# Sheet3_MCU.net
KiCad netlist of a schematic drawn in Altium Designer
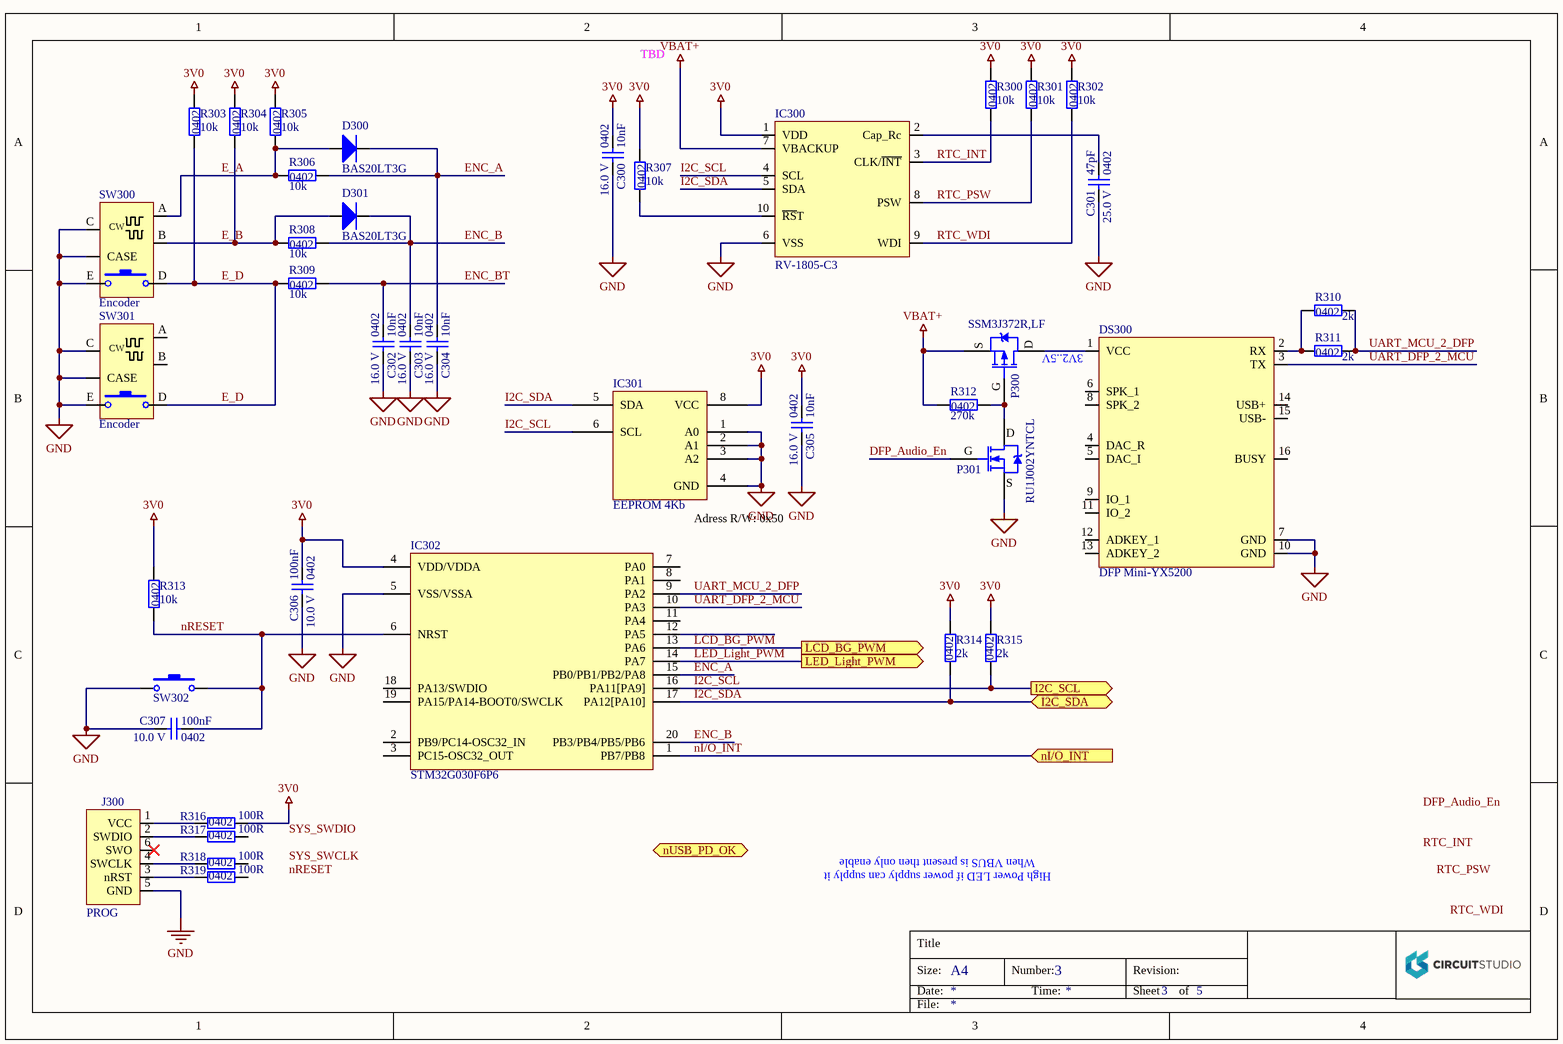
[diagram p0: Sheet3_MCU.SchDoc]

(export (version "E")
  (design (tool "Eeschema 10.0.6"))
  (components
    (comp (ref "C300")
      (value "C 10nF 0402 16V")
      (footprint "0402")
      (description "CAP CER 10000PF 16V Y5V 0402")
      (fields
        (field (name "MANUFACTURER") "Samsung Electro-Mechanics")
        (field (name "MANUFACTURER PART NUMBER") "CL05F103ZO5NNNC")
        (field (name "CAPACITANCE") "10nF")
        (field (name "VOLTAGE") "16.0 V")
      )
      (libsource (lib "CS_Part_Library") (part "CAP_10nF_16V_0402"))
    )
    (comp (ref "C301")
      (value "C 47pF 0402 25V")
      (footprint "0402")
      (description "CAP CER 47PF 25V C0G/NP0 0402")
      (fields
        (field (name "MANUFACTURER") "KEMET")
        (field (name "MANUFACTURER PART NUMBER") "C0402C470J3GAC7867")
        (field (name "CAPACITANCE") "47pF")
        (field (name "VOLTAGE") "25.0 V")
      )
      (libsource (lib "CS_Part_Library") (part "CAP_47pF_25V_0402"))
    )
    (comp (ref "C302")
      (value "C 10nF 0402 16V")
      (footprint "0402")
      (description "CAP CER 10000PF 16V Y5V 0402")
      (fields
        (field (name "MANUFACTURER") "Samsung Electro-Mechanics")
        (field (name "MANUFACTURER PART NUMBER") "CL05F103ZO5NNNC")
        (field (name "CAPACITANCE") "10nF")
        (field (name "VOLTAGE") "16.0 V")
      )
      (libsource (lib "CS_Part_Library") (part "CAP_10nF_16V_0402"))
    )
    (comp (ref "C303")
      (value "C 10nF 0402 16V")
      (footprint "0402")
      (description "CAP CER 10000PF 16V Y5V 0402")
      (fields
        (field (name "MANUFACTURER") "Samsung Electro-Mechanics")
        (field (name "MANUFACTURER PART NUMBER") "CL05F103ZO5NNNC")
        (field (name "CAPACITANCE") "10nF")
        (field (name "VOLTAGE") "16.0 V")
      )
      (libsource (lib "CS_Part_Library") (part "CAP_10nF_16V_0402"))
    )
    (comp (ref "C304")
      (value "C 10nF 0402 16V")
      (footprint "0402")
      (description "CAP CER 10000PF 16V Y5V 0402")
      (fields
        (field (name "MANUFACTURER") "Samsung Electro-Mechanics")
        (field (name "MANUFACTURER PART NUMBER") "CL05F103ZO5NNNC")
        (field (name "CAPACITANCE") "10nF")
        (field (name "VOLTAGE") "16.0 V")
      )
      (libsource (lib "CS_Part_Library") (part "CAP_10nF_16V_0402"))
    )
    (comp (ref "C305")
      (value "C 10nF 0402 16V")
      (footprint "0402")
      (description "CAP CER 10000PF 16V Y5V 0402")
      (fields
        (field (name "MANUFACTURER") "Samsung Electro-Mechanics")
        (field (name "MANUFACTURER PART NUMBER") "CL05F103ZO5NNNC")
        (field (name "CAPACITANCE") "10nF")
        (field (name "VOLTAGE") "16.0 V")
      )
      (libsource (lib "CS_Part_Library") (part "CAP_10nF_16V_0402"))
    )
    (comp (ref "C306")
      (value "C 100nF 0402 10V")
      (footprint "0402")
      (description "CAP CER 0.1UF 10V X5R 0402")
      (fields
        (field (name "MANUFACTURER") "Samsung Electro-Mechanics")
        (field (name "MANUFACTURER PART NUMBER") "CL05A104MP5NNNC")
        (field (name "CAPACITANCE") "100nF")
        (field (name "VOLTAGE") "10.0 V")
      )
      (libsource (lib "CS_Part_Library") (part "CAP_100nF_10V_0402"))
    )
    (comp (ref "C307")
      (value "C 100nF 0402 10V")
      (footprint "0402")
      (description "CAP CER 0.1UF 10V X5R 0402")
      (fields
        (field (name "MANUFACTURER") "Samsung Electro-Mechanics")
        (field (name "MANUFACTURER PART NUMBER") "CL05A104MP5NNNC")
        (field (name "CAPACITANCE") "100nF")
        (field (name "VOLTAGE") "10.0 V")
      )
      (libsource (lib "CS_Part_Library") (part "CAP_100nF_10V_0402"))
    )
    (comp (ref "D300")
      (value "BAS20LT3G")
      (footprint "SOT-23-3")
      (description "DIODE GP 200V 200MA SOT23-3")
      (fields (field (name "MANUFACTURER") "onsemi") (field (name "MANUFACTURER PART NUMBER") "BAS20LT3G"))
      (libsource (lib "Symbols") (part "D_LL_200V_200mA"))
    )
    (comp (ref "D301")
      (value "BAS20LT3G")
      (footprint "SOT-23-3")
      (description "DIODE GP 200V 200MA SOT23-3")
      (fields (field (name "MANUFACTURER") "onsemi") (field (name "MANUFACTURER PART NUMBER") "BAS20LT3G"))
      (libsource (lib "Symbols") (part "D_LL_200V_200mA"))
    )
    (comp (ref "DS300")
      (value "DFP Mini-YX5200")
      (footprint "DFP_Player_Mini")
      (description "Mini-YX5200 Audio MP3 Modul")
      (fields (field (name "MANUFACTURER") "DFRobot") (field (name "MANUFACTURER PART NUMBER") "DFR0299"))
      (libsource (lib "CS_Part_Library") (part "DFP_Player_mini"))
    )
    (comp (ref "IC300")
      (value "RV-1805-C3")
      (footprint "SON-6")
      (description "IC RTC CLK/CALENDAR I2C 10SON")
      (fields
        (field (name "MANUFACTURER") "Micro Crystal AG")
        (field (name "MANUFACTURER PART NUMBER") "RV-1805-C3-32.768KHZ-2PPM-TA-QA")
      )
      (libsource (lib "CS_Part_Library") (part "IC_RTC_1805-C3"))
    )
    (comp (ref "IC301")
      (value "EEPROM 4Kb")
      (footprint "TSSOP-8_4.4mm")
      (description "IC EEPROM 4KBIT I2C 1MHZ 8TSSOP")
      (fields
        (field (name "MANUFACTURER") "Microchip Technology")
        (field (name "MANUFACTURER PART NUMBER") "AT34C04-X5M-T")
      )
      (libsource (lib "CS_Part_Library") (part "IC_EEPROM_4Kb"))
    )
    (comp (ref "IC302")
      (value "STM32G030F6P6")
      (footprint "TSSOP-20")
      (description "IC MCU 32BIT 32KB FLASH 20TSSOP")
      (fields (field (name "MANUFACTURER") "STMicroelectronics"))
      (libsource (lib "CS_Part_Library") (part "IC_MCU_STM32G030F6P6"))
    )
    (comp (ref "J300")
      (value "PROG")
      (footprint "J_TC2030-IDC-FP")
      (description "SWD Programmer")
      (fields (field (name "MANUFACTURER") "Tag_connect") (field (name "MANUFACTURER PART NUMBER") "TC2030"))
      (libsource (lib "CS_Part_Library") (part "J_TC2030-IDC-FP"))
    )
    (comp (ref "P300")
      (value "P PMOS 30V 6A")
      (footprint "SOT-23-3-F")
      (description "MOSFET P-CH 30V 6A SOT23F")
      (fields
        (field (name "MANUFACTURER") "Toshiba Semiconductor and Storage")
        (field (name "MANUFACTURER PART NUMBER") "SSM3J372R,LF")
      )
      (libsource (lib "CS_Part_Library") (part "P_PCH_30V_1W"))
    )
    (comp (ref "P301")
      (value "P_NCH_50V_150mW")
      (footprint "UMT3F")
      (description "MOSFET N-CH 50V 200MA UMT3F")
      (fields
        (field (name "MANUFACTURER") "Rohm Semiconductor")
        (field (name "MANUFACTURER PART NUMBER") "RU1J002YNTCL")
      )
      (libsource (lib "CS_Part_Library") (part "P_NCH_50V_150mW"))
    )
    (comp (ref "R300")
      (value "R 10k 0402")
      (footprint "0402")
      (description "RES 10K OHM 1% 1/16W 0402")
      (fields
        (field (name "MANUFACTURER") "YAGEO")
        (field (name "MANUFACTURER PART NUMBER") "RC0402FR-0710KL")
        (field (name "RESISTANCE") "10k")
      )
      (libsource (lib "") (part "R_10k_0402_1"))
    )
    (comp (ref "R301")
      (value "R 10k 0402")
      (footprint "0402")
      (description "RES 10K OHM 1% 1/16W 0402")
      (fields
        (field (name "MANUFACTURER") "YAGEO")
        (field (name "MANUFACTURER PART NUMBER") "RC0402FR-0710KL")
        (field (name "RESISTANCE") "10k")
      )
      (libsource (lib "") (part "R_10k_0402_1"))
    )
    (comp (ref "R302")
      (value "R 10k 0402")
      (footprint "0402")
      (description "RES 10K OHM 1% 1/16W 0402")
      (fields
        (field (name "MANUFACTURER") "YAGEO")
        (field (name "MANUFACTURER PART NUMBER") "RC0402FR-0710KL")
        (field (name "RESISTANCE") "10k")
      )
      (libsource (lib "") (part "R_10k_0402_1"))
    )
    (comp (ref "R303")
      (value "R 10k 0402")
      (footprint "0402")
      (description "RES 10K OHM 1% 1/16W 0402")
      (fields
        (field (name "MANUFACTURER") "YAGEO")
        (field (name "MANUFACTURER PART NUMBER") "RC0402FR-0710KL")
        (field (name "RESISTANCE") "10k")
      )
      (libsource (lib "") (part "R_10k_0402_1"))
    )
    (comp (ref "R304")
      (value "R 10k 0402")
      (footprint "0402")
      (description "RES 10K OHM 1% 1/16W 0402")
      (fields
        (field (name "MANUFACTURER") "YAGEO")
        (field (name "MANUFACTURER PART NUMBER") "RC0402FR-0710KL")
        (field (name "RESISTANCE") "10k")
      )
      (libsource (lib "") (part "R_10k_0402_1"))
    )
    (comp (ref "R305")
      (value "R 10k 0402")
      (footprint "0402")
      (description "RES 10K OHM 1% 1/16W 0402")
      (fields
        (field (name "MANUFACTURER") "YAGEO")
        (field (name "MANUFACTURER PART NUMBER") "RC0402FR-0710KL")
        (field (name "RESISTANCE") "10k")
      )
      (libsource (lib "") (part "R_10k_0402_1"))
    )
    (comp (ref "R306")
      (value "R 10k 0402")
      (footprint "0402")
      (description "RES 10K OHM 1% 1/16W 0402")
      (fields
        (field (name "MANUFACTURER") "YAGEO")
        (field (name "MANUFACTURER PART NUMBER") "RC0402FR-0710KL")
        (field (name "RESISTANCE") "10k")
      )
      (libsource (lib "CS_Part_Library") (part "R_10k_0402"))
    )
    (comp (ref "R307")
      (value "R 10k 0402")
      (footprint "0402")
      (description "RES 10K OHM 1% 1/16W 0402")
      (fields
        (field (name "MANUFACTURER") "YAGEO")
        (field (name "MANUFACTURER PART NUMBER") "RC0402FR-0710KL")
        (field (name "RESISTANCE") "10k")
      )
      (libsource (lib "") (part "R_10k_0402_1"))
    )
    (comp (ref "R308")
      (value "R 10k 0402")
      (footprint "0402")
      (description "RES 10K OHM 1% 1/16W 0402")
      (fields
        (field (name "MANUFACTURER") "YAGEO")
        (field (name "MANUFACTURER PART NUMBER") "RC0402FR-0710KL")
        (field (name "RESISTANCE") "10k")
      )
      (libsource (lib "CS_Part_Library") (part "R_10k_0402"))
    )
    (comp (ref "R309")
      (value "R 10k 0402")
      (footprint "0402")
      (description "RES 10K OHM 1% 1/16W 0402")
      (fields
        (field (name "MANUFACTURER") "YAGEO")
        (field (name "MANUFACTURER PART NUMBER") "RC0402FR-0710KL")
        (field (name "RESISTANCE") "10k")
      )
      (libsource (lib "CS_Part_Library") (part "R_10k_0402"))
    )
    (comp (ref "R310")
      (value "R 2k 0402")
      (footprint "0402")
      (description "RES 2K OHM 1% 1/16W 0402")
      (fields
        (field (name "MANUFACTURER") "Stackpole Electronics Inc")
        (field (name "MANUFACTURER PART NUMBER") "RMCF0402FT2K00")
        (field (name "RESISTANCE") "2k")
      )
      (libsource (lib "") (part "R_2k_0402_1"))
    )
    (comp (ref "R311")
      (value "R 2k 0402")
      (footprint "0402")
      (description "RES 2K OHM 1% 1/16W 0402")
      (fields
        (field (name "MANUFACTURER") "Stackpole Electronics Inc")
        (field (name "MANUFACTURER PART NUMBER") "RMCF0402FT2K00")
        (field (name "RESISTANCE") "2k")
      )
      (libsource (lib "") (part "R_2k_0402_1"))
    )
    (comp (ref "R312")
      (value "R 270k 0402")
      (footprint "0402")
      (description "RES 270K OHM 1% 1/16W 0402")
      (fields
        (field (name "MANUFACTURER") "YAGEO")
        (field (name "MANUFACTURER PART NUMBER") "RC0402FR-07270KL")
        (field (name "RESISTANCE") "270k")
      )
      (libsource (lib "CS_Part_Library") (part "R_270k_0402"))
    )
    (comp (ref "R313")
      (value "R 10k 0402")
      (footprint "0402")
      (description "RES 10K OHM 1% 1/16W 0402")
      (fields
        (field (name "MANUFACTURER") "YAGEO")
        (field (name "MANUFACTURER PART NUMBER") "RC0402FR-0710KL")
        (field (name "RESISTANCE") "10k")
      )
      (libsource (lib "") (part "R_10k_0402_1"))
    )
    (comp (ref "R314")
      (value "R 2k 0402")
      (footprint "0402")
      (description "RES 2K OHM 1% 1/16W 0402")
      (fields
        (field (name "MANUFACTURER") "Stackpole Electronics Inc")
        (field (name "MANUFACTURER PART NUMBER") "RMCF0402FT2K00")
        (field (name "RESISTANCE") "2k")
      )
      (libsource (lib "CS_Part_Library") (part "R_2k_0402"))
    )
    (comp (ref "R315")
      (value "R 2k 0402")
      (footprint "0402")
      (description "RES 2K OHM 1% 1/16W 0402")
      (fields
        (field (name "MANUFACTURER") "Stackpole Electronics Inc")
        (field (name "MANUFACTURER PART NUMBER") "RMCF0402FT2K00")
        (field (name "RESISTANCE") "2k")
      )
      (libsource (lib "CS_Part_Library") (part "R_2k_0402"))
    )
    (comp (ref "R316")
      (value "R 100R 0402")
      (footprint "0402")
      (description "RES 100 OHM 1% 1/16W 0402")
      (fields
        (field (name "MANUFACTURER") "Stackpole Electronics Inc")
        (field (name "MANUFACTURER PART NUMBER") "RMCF0402FT100R")
        (field (name "RESISTANCE") "100R")
      )
      (libsource (lib "Symbols") (part "R_100R_0402"))
    )
    (comp (ref "R317")
      (value "R 100R 0402")
      (footprint "0402")
      (description "RES 100 OHM 1% 1/16W 0402")
      (fields
        (field (name "MANUFACTURER") "Stackpole Electronics Inc")
        (field (name "MANUFACTURER PART NUMBER") "RMCF0402FT100R")
        (field (name "RESISTANCE") "100R")
      )
      (libsource (lib "Symbols") (part "R_100R_0402"))
    )
    (comp (ref "R318")
      (value "R 100R 0402")
      (footprint "0402")
      (description "RES 100 OHM 1% 1/16W 0402")
      (fields
        (field (name "MANUFACTURER") "Stackpole Electronics Inc")
        (field (name "MANUFACTURER PART NUMBER") "RMCF0402FT100R")
        (field (name "RESISTANCE") "100R")
      )
      (libsource (lib "Symbols") (part "R_100R_0402"))
    )
    (comp (ref "R319")
      (value "R 100R 0402")
      (footprint "0402")
      (description "RES 100 OHM 1% 1/16W 0402")
      (fields
        (field (name "MANUFACTURER") "Stackpole Electronics Inc")
        (field (name "MANUFACTURER PART NUMBER") "RMCF0402FT100R")
        (field (name "RESISTANCE") "100R")
      )
      (libsource (lib "Symbols") (part "R_100R_0402"))
    )
    (comp (ref "SW300")
      (value "Encoder")
      (footprint "PEC11R")
      (description "ROTARY ENCODER MECHANICAL 12PPR")
      (fields
        (field (name "MANUFACTURER") "Bourns Inc.")
        (field (name "MANUFACTURER PART NUMBER") "PEC11R-4220F-S0012")
      )
      (libsource (lib "CS_Part_Library") (part "ENC_12_THT"))
    )
    (comp (ref "SW301")
      (value "Encoder")
      (footprint "PEC11R")
      (description "ROTARY ENCODER MECHANICAL 12PPR")
      (fields
        (field (name "MANUFACTURER") "Bourns Inc.")
        (field (name "MANUFACTURER PART NUMBER") "PEC11R-4220F-S0012")
      )
      (libsource (lib "CS_Part_Library") (part "ENC_12_THT"))
    )
    (comp (ref "SW302")
      (value "SW")
      (footprint "SW_PTS810")
      (description "SWITCH TACTILE SPST-NO 0.05A 16V")
      (fields
        (field (name "MANUFACTURER") "C&K")
        (field (name "MANUFACTURER PART NUMBER") "PTS810 SJM 250 SMTR LFS")
      )
      (libsource (lib "CS_Part_Library") (part "SW_TactileSW_V"))
    )
  )
  (nets
    (net (code "1") (name "/DFP_Audio_En") (class "Default")
      (node (ref "P301") (pin "1") (pinfunction "G_1") (pintype "passive"))
    )
    (net (code "2") (name "/ENC_A") (class "Default")
      (node (ref "C304") (pin "2") (pinfunction "2_2") (pintype "passive"))
      (node (ref "D300") (pin "3") (pinfunction "K_3") (pintype "passive"))
      (node (ref "IC302") (pin "15") (pinfunction "PB0/PB1/PB2/PA8_15") (pintype "passive"))
      (node (ref "R306") (pin "2") (pinfunction "2_2") (pintype "passive"))
    )
    (net (code "3") (name "/ENC_B") (class "Default")
      (node (ref "C303") (pin "2") (pinfunction "2_2") (pintype "passive"))
      (node (ref "D301") (pin "3") (pinfunction "K_3") (pintype "passive"))
      (node (ref "IC302") (pin "20") (pinfunction "PB3/PB4/PB5/PB6_20") (pintype "passive"))
      (node (ref "R308") (pin "2") (pinfunction "2_2") (pintype "passive"))
    )
    (net (code "4") (name "/ENC_BT") (class "Default")
      (node (ref "C302") (pin "2") (pinfunction "2_2") (pintype "passive"))
      (node (ref "R309") (pin "2") (pinfunction "2_2") (pintype "passive"))
    )
    (net (code "5") (name "/E_A") (class "Default")
      (node (ref "D300") (pin "1") (pinfunction "A_1") (pintype "passive"))
      (node (ref "R305") (pin "1") (pinfunction "1_1") (pintype "passive"))
      (node (ref "R306") (pin "1") (pinfunction "1_1") (pintype "passive"))
      (node (ref "SW300") (pin "A") (pinfunction "A_A") (pintype "passive"))
    )
    (net (code "6") (name "/E_B") (class "Default")
      (node (ref "D301") (pin "1") (pinfunction "A_1") (pintype "passive"))
      (node (ref "R304") (pin "1") (pinfunction "1_1") (pintype "passive"))
      (node (ref "R308") (pin "1") (pinfunction "1_1") (pintype "passive"))
      (node (ref "SW300") (pin "B") (pinfunction "B_B") (pintype "passive"))
    )
    (net (code "7") (name "/E_D") (class "Default")
      (node (ref "R303") (pin "1") (pinfunction "1_1") (pintype "passive"))
      (node (ref "R309") (pin "1") (pinfunction "1_1") (pintype "passive"))
      (node (ref "SW300") (pin "D") (pinfunction "D_D") (pintype "passive"))
      (node (ref "SW301") (pin "D") (pinfunction "D_D") (pintype "passive"))
    )
    (net (code "8") (name "/I2C_SCL") (class "Default")
      (node (ref "IC300") (pin "4") (pinfunction "SCL_4") (pintype "passive"))
      (node (ref "IC301") (pin "6") (pinfunction "SCL_6") (pintype "passive"))
      (node (ref "IC302") (pin "16") (pinfunction "PA11[PA9]_16") (pintype "passive"))
      (node (ref "R315") (pin "1") (pinfunction "1_1") (pintype "passive"))
    )
    (net (code "9") (name "/I2C_SDA") (class "Default")
      (node (ref "IC300") (pin "5") (pinfunction "SDA_5") (pintype "passive"))
      (node (ref "IC301") (pin "5") (pinfunction "SDA_5") (pintype "passive"))
      (node (ref "IC302") (pin "17") (pinfunction "PA12[PA10]_17") (pintype "passive"))
      (node (ref "R314") (pin "1") (pinfunction "1_1") (pintype "passive"))
    )
    (net (code "10") (name "/LCD_BG_PWM") (class "Default")
      (node (ref "IC302") (pin "13") (pinfunction "PA6_13") (pintype "passive"))
    )
    (net (code "11") (name "/LED_Light_PWM") (class "Default")
      (node (ref "IC302") (pin "14") (pinfunction "PA7_14") (pintype "passive"))
    )
    (net (code "12") (name "/RTC_INT") (class "Default")
      (node (ref "IC300") (pin "3") (pinfunction "CLK/~{INT}_3") (pintype "passive"))
      (node (ref "R300") (pin "1") (pinfunction "1_1") (pintype "passive"))
    )
    (net (code "13") (name "/RTC_PSW") (class "Default")
      (node (ref "IC300") (pin "8") (pinfunction "PSW_8") (pintype "passive"))
      (node (ref "R301") (pin "1") (pinfunction "1_1") (pintype "passive"))
    )
    (net (code "14") (name "/RTC_WDI") (class "Default")
      (node (ref "IC300") (pin "9") (pinfunction "WDI_9") (pintype "passive"))
      (node (ref "R302") (pin "1") (pinfunction "1_1") (pintype "passive"))
    )
    (net (code "17") (name "/UART_DFP_2_MCU") (class "Default")
      (node (ref "DS300") (pin "3") (pinfunction "TX_3") (pintype "passive"))
      (node (ref "IC302") (pin "10") (pinfunction "PA3_10") (pintype "passive"))
    )
    (net (code "18") (name "/UART_MCU_2_DFP") (class "Default")
      (node (ref "IC302") (pin "9") (pinfunction "PA2_9") (pintype "passive"))
      (node (ref "R310") (pin "1") (pinfunction "1_1") (pintype "passive"))
      (node (ref "R311") (pin "1") (pinfunction "1_1") (pintype "passive"))
    )
    (net (code "19") (name "/nI{slash}O_INT") (class "Default")
      (node (ref "IC302") (pin "1") (pinfunction "PB7/PB8_1") (pintype "passive"))
    )
    (net (code "20") (name "/nRESET") (class "Default")
      (node (ref "C307") (pin "2") (pinfunction "2_2") (pintype "passive"))
      (node (ref "IC302") (pin "6") (pinfunction "NRST_6") (pintype "passive"))
      (node (ref "R313") (pin "1") (pinfunction "1_1") (pintype "passive"))
      (node (ref "SW302") (pin "3") (pinfunction "2,_3_3") (pintype "passive"))
    )
    (net (code "22") (name "3V0") (class "Default")
      (node (ref "C300") (pin "2") (pinfunction "2_2") (pintype "passive"))
      (node (ref "C305") (pin "2") (pinfunction "2_2") (pintype "passive"))
      (node (ref "C306") (pin "2") (pinfunction "2_2") (pintype "passive"))
      (node (ref "IC300") (pin "1") (pinfunction "VDD_1") (pintype "passive"))
      (node (ref "IC301") (pin "8") (pinfunction "VCC_8") (pintype "passive"))
      (node (ref "IC302") (pin "4") (pinfunction "VDD/VDDA_4") (pintype "passive"))
      (node (ref "R300") (pin "2") (pinfunction "2_2") (pintype "passive"))
      (node (ref "R301") (pin "2") (pinfunction "2_2") (pintype "passive"))
      (node (ref "R302") (pin "2") (pinfunction "2_2") (pintype "passive"))
      (node (ref "R303") (pin "2") (pinfunction "2_2") (pintype "passive"))
      (node (ref "R304") (pin "2") (pinfunction "2_2") (pintype "passive"))
      (node (ref "R305") (pin "2") (pinfunction "2_2") (pintype "passive"))
      (node (ref "R307") (pin "2") (pinfunction "2_2") (pintype "passive"))
      (node (ref "R313") (pin "2") (pinfunction "2_2") (pintype "passive"))
      (node (ref "R314") (pin "2") (pinfunction "2_2") (pintype "passive"))
      (node (ref "R315") (pin "2") (pinfunction "2_2") (pintype "passive"))
      (node (ref "R316") (pin "2") (pinfunction "2_2") (pintype "passive"))
    )
    (net (code "23") (name "GND") (class "Default")
      (node (ref "C300") (pin "1") (pinfunction "1_1") (pintype "passive"))
      (node (ref "C301") (pin "1") (pinfunction "1_1") (pintype "passive"))
      (node (ref "C302") (pin "1") (pinfunction "1_1") (pintype "passive"))
      (node (ref "C303") (pin "1") (pinfunction "1_1") (pintype "passive"))
      (node (ref "C304") (pin "1") (pinfunction "1_1") (pintype "passive"))
      (node (ref "C305") (pin "1") (pinfunction "1_1") (pintype "passive"))
      (node (ref "C306") (pin "1") (pinfunction "1_1") (pintype "passive"))
      (node (ref "C307") (pin "1") (pinfunction "1_1") (pintype "passive"))
      (node (ref "DS300") (pin "10") (pinfunction "GND_10") (pintype "passive"))
      (node (ref "DS300") (pin "7") (pinfunction "GND_7") (pintype "passive"))
      (node (ref "IC300") (pin "6") (pinfunction "VSS_6") (pintype "passive"))
      (node (ref "IC301") (pin "1") (pinfunction "A0_1") (pintype "passive"))
      (node (ref "IC301") (pin "2") (pinfunction "A1_2") (pintype "passive"))
      (node (ref "IC301") (pin "3") (pinfunction "A2_3") (pintype "passive"))
      (node (ref "IC301") (pin "4") (pinfunction "GND_4") (pintype "passive"))
      (node (ref "IC302") (pin "5") (pinfunction "VSS/VSSA_5") (pintype "passive"))
      (node (ref "J300") (pin "5") (pinfunction "GND_5") (pintype "passive"))
      (node (ref "P301") (pin "2") (pinfunction "S_2") (pintype "passive"))
      (node (ref "SW300") (pin "C") (pinfunction "C_C") (pintype "passive"))
      (node (ref "SW300") (pin "CASE") (pinfunction "CASE_CASE") (pintype "passive"))
      (node (ref "SW300") (pin "E") (pinfunction "E_E") (pintype "passive"))
      (node (ref "SW301") (pin "C") (pinfunction "C_C") (pintype "passive"))
      (node (ref "SW301") (pin "CASE") (pinfunction "CASE_CASE") (pintype "passive"))
      (node (ref "SW301") (pin "E") (pinfunction "E_E") (pintype "passive"))
      (node (ref "SW302") (pin "1") (pinfunction "1,_2_1") (pintype "passive"))
    )
    (net (code "24") (name "Net-(DS300-RX)") (class "Default")
      (node (ref "DS300") (pin "2") (pinfunction "RX_2") (pintype "passive"))
      (node (ref "R310") (pin "2") (pinfunction "2_2") (pintype "passive"))
      (node (ref "R311") (pin "2") (pinfunction "2_2") (pintype "passive"))
    )
    (net (code "25") (name "Net-(DS300-VCC)") (class "Default")
      (node (ref "DS300") (pin "1") (pinfunction "VCC_1") (pintype "passive"))
      (node (ref "P300") (pin "3") (pinfunction "D_3") (pintype "passive"))
    )
    (net (code "26") (name "Net-(IC300-Cap_Rc)") (class "Default")
      (node (ref "C301") (pin "2") (pinfunction "2_2") (pintype "passive"))
      (node (ref "IC300") (pin "2") (pinfunction "Cap_Rc_2") (pintype "passive"))
    )
    (net (code "27") (name "Net-(IC300-~{RS}T)") (class "Default")
      (node (ref "IC300") (pin "10") (pinfunction "~{RS}T_10") (pintype "passive"))
      (node (ref "R307") (pin "1") (pinfunction "1_1") (pintype "passive"))
    )
    (net (code "28") (name "Net-(J300-SWCLK)") (class "Default")
      (node (ref "J300") (pin "4") (pinfunction "SWCLK_4") (pintype "passive"))
      (node (ref "R318") (pin "1") (pinfunction "1_1") (pintype "passive"))
    )
    (net (code "29") (name "Net-(J300-SWDIO)") (class "Default")
      (node (ref "J300") (pin "2") (pinfunction "SWDIO_2") (pintype "passive"))
      (node (ref "R317") (pin "1") (pinfunction "1_1") (pintype "passive"))
    )
    (net (code "30") (name "Net-(J300-VCC)") (class "Default")
      (node (ref "J300") (pin "1") (pinfunction "VCC_1") (pintype "passive"))
      (node (ref "R316") (pin "1") (pinfunction "1_1") (pintype "passive"))
    )
    (net (code "31") (name "Net-(J300-nRST)") (class "Default")
      (node (ref "J300") (pin "3") (pinfunction "nRST_3") (pintype "passive"))
      (node (ref "R319") (pin "1") (pinfunction "1_1") (pintype "passive"))
    )
    (net (code "32") (name "Net-(P300-G)") (class "Default")
      (node (ref "P300") (pin "1") (pinfunction "G_1") (pintype "passive"))
      (node (ref "P301") (pin "3") (pinfunction "D_3") (pintype "passive"))
      (node (ref "R312") (pin "1") (pinfunction "1_1") (pintype "passive"))
    )
    (net (code "33") (name "VBAT+") (class "Default")
      (node (ref "IC300") (pin "7") (pinfunction "VBACKUP_7") (pintype "passive"))
      (node (ref "P300") (pin "2") (pinfunction "S_2") (pintype "passive"))
      (node (ref "R312") (pin "2") (pinfunction "2_2") (pintype "passive"))
    )
    (net (code "34") (name "unconnected-(DS300-ADKEY_1-Pad12)") (class "Default")
      (node (ref "DS300") (pin "12") (pinfunction "ADKEY_1_12") (pintype "passive"))
    )
    (net (code "35") (name "unconnected-(DS300-ADKEY_2-Pad13)") (class "Default")
      (node (ref "DS300") (pin "13") (pinfunction "ADKEY_2_13") (pintype "passive"))
    )
    (net (code "36") (name "unconnected-(DS300-BUSY-Pad16)") (class "Default")
      (node (ref "DS300") (pin "16") (pinfunction "BUSY_16") (pintype "passive"))
    )
    (net (code "37") (name "unconnected-(DS300-DAC_I-Pad5)") (class "Default")
      (node (ref "DS300") (pin "5") (pinfunction "DAC_I_5") (pintype "passive"))
    )
    (net (code "38") (name "unconnected-(DS300-DAC_R-Pad4)") (class "Default")
      (node (ref "DS300") (pin "4") (pinfunction "DAC_R_4") (pintype "passive"))
    )
    (net (code "39") (name "unconnected-(DS300-IO_1-Pad9)") (class "Default")
      (node (ref "DS300") (pin "9") (pinfunction "IO_1_9") (pintype "passive"))
    )
    (net (code "40") (name "unconnected-(DS300-IO_2-Pad11)") (class "Default")
      (node (ref "DS300") (pin "11") (pinfunction "IO_2_11") (pintype "passive"))
    )
    (net (code "41") (name "unconnected-(DS300-SPK_1-Pad6)") (class "Default")
      (node (ref "DS300") (pin "6") (pinfunction "SPK_1_6") (pintype "passive"))
    )
    (net (code "42") (name "unconnected-(DS300-SPK_2-Pad8)") (class "Default")
      (node (ref "DS300") (pin "8") (pinfunction "SPK_2_8") (pintype "passive"))
    )
    (net (code "43") (name "unconnected-(DS300-USB+-Pad14)") (class "Default")
      (node (ref "DS300") (pin "14") (pinfunction "USB+_14") (pintype "passive"))
    )
    (net (code "44") (name "unconnected-(DS300-USB--Pad15)") (class "Default")
      (node (ref "DS300") (pin "15") (pinfunction "USB-_15") (pintype "passive"))
    )
    (net (code "45") (name "unconnected-(IC302-PA0-Pad7)") (class "Default")
      (node (ref "IC302") (pin "7") (pinfunction "PA0_7") (pintype "passive"))
    )
    (net (code "46") (name "unconnected-(IC302-PA1-Pad8)") (class "Default")
      (node (ref "IC302") (pin "8") (pinfunction "PA1_8") (pintype "passive"))
    )
    (net (code "47") (name "unconnected-(IC302-PA4-Pad11)") (class "Default")
      (node (ref "IC302") (pin "11") (pinfunction "PA4_11") (pintype "passive"))
    )
    (net (code "48") (name "unconnected-(IC302-PA5-Pad12)") (class "Default")
      (node (ref "IC302") (pin "12") (pinfunction "PA5_12") (pintype "passive"))
    )
    (net (code "49") (name "unconnected-(IC302-PA13{slash}SWDIO-Pad18)") (class "Default")
      (node (ref "IC302") (pin "18") (pinfunction "PA13/SWDIO_18") (pintype "passive"))
    )
    (net (code "50") (name "unconnected-(IC302-PA15{slash}PA14-BOOT0{slash}SWCLK-Pad19)") (class "Default")
      (node (ref "IC302") (pin "19") (pinfunction "PA15/PA14-BOOT0/SWCLK_19") (pintype "passive"))
    )
    (net (code "51") (name "unconnected-(IC302-PB9{slash}PC14-OSC32_IN-Pad2)") (class "Default")
      (node (ref "IC302") (pin "2") (pinfunction "PB9/PC14-OSC32_IN_2") (pintype "passive"))
    )
    (net (code "52") (name "unconnected-(IC302-PC15-OSC32_OUT-Pad3)") (class "Default")
      (node (ref "IC302") (pin "3") (pinfunction "PC15-OSC32_OUT_3") (pintype "passive"))
    )
    (net (code "53") (name "unconnected-(J300-SWO-Pad6)") (class "Default")
      (node (ref "J300") (pin "6") (pinfunction "SWO_6") (pintype "passive+no_connect"))
    )
    (net (code "54") (name "unconnected-(R317-Pad2)") (class "Default")
      (node (ref "R317") (pin "2") (pinfunction "2_2") (pintype "passive"))
    )
    (net (code "55") (name "unconnected-(R318-Pad2)") (class "Default")
      (node (ref "R318") (pin "2") (pinfunction "2_2") (pintype "passive"))
    )
    (net (code "56") (name "unconnected-(R319-Pad2)") (class "Default")
      (node (ref "R319") (pin "2") (pinfunction "2_2") (pintype "passive"))
    )
    (net (code "57") (name "unconnected-(SW301-PadA)") (class "Default")
      (node (ref "SW301") (pin "A") (pinfunction "A_A") (pintype "passive"))
    )
    (net (code "58") (name "unconnected-(SW301-PadB)") (class "Default")
      (node (ref "SW301") (pin "B") (pinfunction "B_B") (pintype "passive"))
    )
  )
)
